# BSK.net
KiCad netlist of a schematic drawn in EAGLE
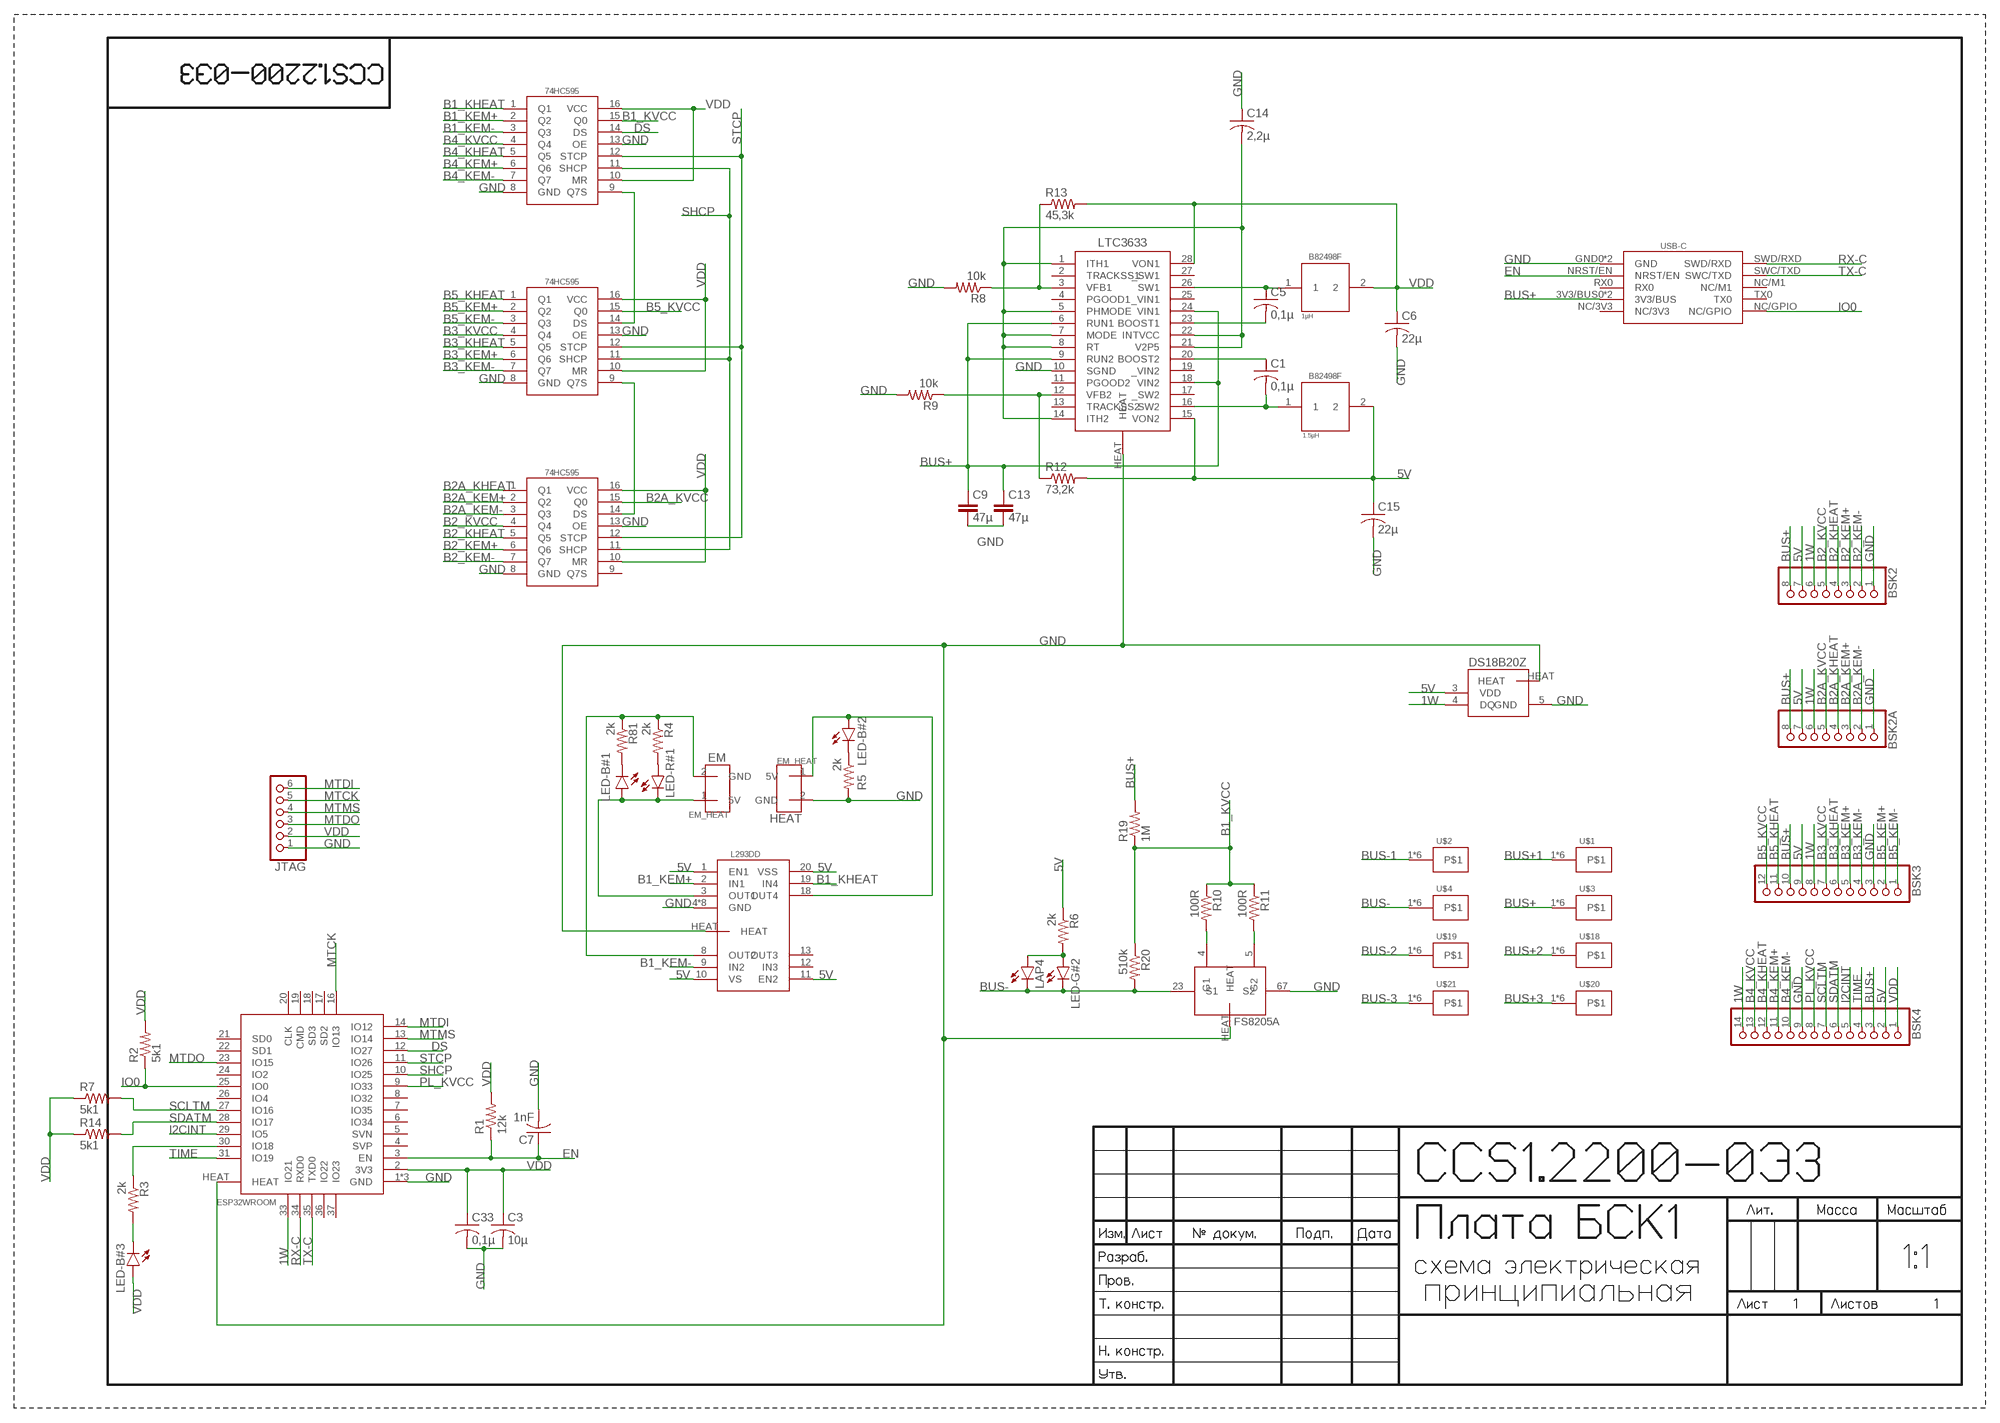
[diagram p0: schematic, sheet 1]

(export (version "E")
  (design (tool "Eeschema 10.0.6"))
  (components
    (comp (ref "74HC595#1")
      (value "74HC595")
      (footprint "eagle-import:74HC595")
      (libsource (lib "eagle-import") (part "74HC595"))
    )
    (comp (ref "74HC595#2")
      (value "74HC595")
      (footprint "eagle-import:74HC595")
      (libsource (lib "eagle-import") (part "74HC595"))
    )
    (comp (ref "74HC595#3")
      (value "74HC595")
      (footprint "eagle-import:74HC595")
      (libsource (lib "eagle-import") (part "74HC595"))
    )
    (comp (ref "B82498F#1")
      (value "1µH")
      (footprint "eagle-import:B82498F")
      (libsource (lib "eagle-import") (part "B82498F"))
    )
    (comp (ref "B82498F#2")
      (value "B82498F")
      (footprint "eagle-import:B82498F")
      (libsource (lib "eagle-import") (part "B82498F"))
    )
    (comp (ref "BSK2")
      (value "PINHD-1X8")
      (footprint "eagle-import:1X08")
      (libsource (lib "eagle-import") (part "PINHD-1X8"))
    )
    (comp (ref "BSK2A")
      (value "PINHD-1X8")
      (footprint "eagle-import:1X08")
      (libsource (lib "eagle-import") (part "PINHD-1X8"))
    )
    (comp (ref "BSK3")
      (value "PINHD-1X12")
      (footprint "eagle-import:1X12")
      (libsource (lib "eagle-import") (part "PINHD-1X12"))
    )
    (comp (ref "BSK4")
      (value "PINHD-1X14")
      (footprint "eagle-import:1X14")
      (libsource (lib "eagle-import") (part "PINHD-1X14"))
    )
    (comp (ref "C1")
      (value "0,1µ")
      (footprint "eagle-import:C0603")
      (libsource (lib "eagle-import") (part "C-USC0603"))
    )
    (comp (ref "C3")
      (value "10µ")
      (footprint "eagle-import:C1206")
      (libsource (lib "eagle-import") (part "C-USC1206"))
    )
    (comp (ref "C5")
      (value "0,1µ")
      (footprint "eagle-import:C0603")
      (libsource (lib "eagle-import") (part "C-USC0603"))
    )
    (comp (ref "C6")
      (value "22µ")
      (footprint "eagle-import:C1206")
      (libsource (lib "eagle-import") (part "C-USC1206"))
    )
    (comp (ref "C7")
      (value "1nF")
      (footprint "eagle-import:C0603")
      (libsource (lib "eagle-import") (part "C-USC0603"))
    )
    (comp (ref "C9")
      (value "47µ")
      (footprint "eagle-import:C1210")
      (libsource (lib "eagle-import") (part "C-EUC1210"))
    )
    (comp (ref "C13")
      (value "47µ")
      (footprint "eagle-import:C1210")
      (libsource (lib "eagle-import") (part "C-EUC1210"))
    )
    (comp (ref "C14")
      (value "2,2µ")
      (footprint "eagle-import:C0603")
      (libsource (lib "eagle-import") (part "C-USC0603"))
    )
    (comp (ref "C15")
      (value "22µ")
      (footprint "eagle-import:C1206")
      (libsource (lib "eagle-import") (part "C-USC1206"))
    )
    (comp (ref "C33")
      (value "0,1µ")
      (footprint "eagle-import:C0603")
      (libsource (lib "eagle-import") (part "C-USC0603"))
    )
    (comp (ref "DS18B20Z")
      (value "DS18B20Z")
      (footprint "eagle-import:DS18B20Z")
      (libsource (lib "eagle-import") (part "DS18B20Z"))
    )
    (comp (ref "EM")
      (value "EM_HEAT")
      (footprint "eagle-import:EM_HEAT")
      (libsource (lib "eagle-import") (part "EM_HEAT"))
    )
    (comp (ref "FS8205A")
      (value "FS8205A+")
      (footprint "eagle-import:FS8205A+")
      (libsource (lib "eagle-import") (part "FS8205A+"))
    )
    (comp (ref "HEATER")
      (value "EM_HEAT")
      (footprint "eagle-import:EM_HEAT")
      (libsource (lib "eagle-import") (part "EM_HEAT"))
    )
    (comp (ref "JTAG")
      (value "PINHD-1X6")
      (footprint "eagle-import:1X06")
      (libsource (lib "eagle-import") (part "PINHD-1X6"))
    )
    (comp (ref "L293DD")
      (value "L293DD")
      (footprint "eagle-import:L293DD")
      (libsource (lib "eagle-import") (part "L293DD"))
    )
    (comp (ref "LAP4")
      (value "LAP4-BOTTOM")
      (footprint "eagle-import:P47F-BOTTOM")
      (libsource (lib "eagle-import") (part "P4-BOTTOMLA"))
    )
    (comp (ref "LED-B#1")
      (value "LEDCHIPLED_0603")
      (footprint "eagle-import:CHIPLED_0603")
      (libsource (lib "eagle-import") (part "LEDCHIPLED_0603"))
    )
    (comp (ref "LED-B#2")
      (value "LEDCHIPLED_0603")
      (footprint "eagle-import:CHIPLED_0603")
      (libsource (lib "eagle-import") (part "LEDCHIPLED_0603"))
    )
    (comp (ref "LED-B#3")
      (value "LEDCHIPLED_0603")
      (footprint "eagle-import:CHIPLED_0603")
      (libsource (lib "eagle-import") (part "LEDCHIPLED_0603"))
    )
    (comp (ref "LED-G#2")
      (value "LEDCHIPLED_0603")
      (footprint "eagle-import:CHIPLED_0603")
      (libsource (lib "eagle-import") (part "LEDCHIPLED_0603"))
    )
    (comp (ref "LED-R#1")
      (value "LEDCHIPLED_0603")
      (footprint "eagle-import:CHIPLED_0603")
      (libsource (lib "eagle-import") (part "LEDCHIPLED_0603"))
    )
    (comp (ref "LTC3633")
      (value "LTC3633")
      (footprint "eagle-import:LTC3633")
      (libsource (lib "eagle-import") (part "LTC3633"))
    )
    (comp (ref "R1")
      (value "12k")
      (footprint "eagle-import:R0603")
      (libsource (lib "eagle-import") (part "R-US_R0603"))
    )
    (comp (ref "R2")
      (value "5k1")
      (footprint "eagle-import:R0603")
      (libsource (lib "eagle-import") (part "R-US_R0603"))
    )
    (comp (ref "R3")
      (value "2k")
      (footprint "eagle-import:R0603")
      (libsource (lib "eagle-import") (part "R-US_R0603"))
    )
    (comp (ref "R4")
      (value "2k")
      (footprint "eagle-import:R0603")
      (libsource (lib "eagle-import") (part "R-US_R0603"))
    )
    (comp (ref "R5")
      (value "2k")
      (footprint "eagle-import:R0603")
      (libsource (lib "eagle-import") (part "R-US_R0603"))
    )
    (comp (ref "R6")
      (value "2k")
      (footprint "eagle-import:R0603")
      (libsource (lib "eagle-import") (part "R-US_R0603"))
    )
    (comp (ref "R7")
      (value "5k1")
      (footprint "eagle-import:R0603")
      (libsource (lib "eagle-import") (part "R-US_R0603"))
    )
    (comp (ref "R8")
      (value "10k")
      (footprint "eagle-import:R0603")
      (libsource (lib "eagle-import") (part "R-US_R0603"))
    )
    (comp (ref "R9")
      (value "10k")
      (footprint "eagle-import:R0603")
      (libsource (lib "eagle-import") (part "R-US_R0603"))
    )
    (comp (ref "R10")
      (value "100R")
      (footprint "eagle-import:R0603")
      (libsource (lib "eagle-import") (part "R-US_R0603"))
    )
    (comp (ref "R11")
      (value "100R")
      (footprint "eagle-import:R0603")
      (libsource (lib "eagle-import") (part "R-US_R0603"))
    )
    (comp (ref "R12")
      (value "73,2k")
      (footprint "eagle-import:R0603")
      (libsource (lib "eagle-import") (part "R-US_R0603"))
    )
    (comp (ref "R13")
      (value "45,3k")
      (footprint "eagle-import:R0603")
      (libsource (lib "eagle-import") (part "R-US_R0603"))
    )
    (comp (ref "R14")
      (value "5k1")
      (footprint "eagle-import:R0603")
      (libsource (lib "eagle-import") (part "R-US_R0603"))
    )
    (comp (ref "R19")
      (value "1M")
      (footprint "eagle-import:R0603")
      (libsource (lib "eagle-import") (part "R-US_R0603"))
    )
    (comp (ref "R20")
      (value "510k")
      (footprint "eagle-import:R0603")
      (libsource (lib "eagle-import") (part "R-US_R0603"))
    )
    (comp (ref "R81")
      (value "2k")
      (footprint "eagle-import:R0603")
      (libsource (lib "eagle-import") (part "R-US_R0603"))
    )
    (comp (ref "U$1")
      (value "KCONNECT")
      (footprint "eagle-import:KCONNECT")
      (libsource (lib "eagle-import") (part "KCONNECT"))
    )
    (comp (ref "U$2")
      (value "KCONNECT")
      (footprint "eagle-import:KCONNECT")
      (libsource (lib "eagle-import") (part "KCONNECT"))
    )
    (comp (ref "U$3")
      (value "KCONNECT")
      (footprint "eagle-import:KCONNECT")
      (libsource (lib "eagle-import") (part "KCONNECT"))
    )
    (comp (ref "U$4")
      (value "KCONNECT")
      (footprint "eagle-import:KCONNECT")
      (libsource (lib "eagle-import") (part "KCONNECT"))
    )
    (comp (ref "U$13")
      (value "ESP32WROOM")
      (footprint "eagle-import:ESP32WROOM")
      (libsource (lib "eagle-import") (part "ESP32WROOM"))
    )
    (comp (ref "U$18")
      (value "KCONNECT")
      (footprint "eagle-import:KCONNECT")
      (libsource (lib "eagle-import") (part "KCONNECT"))
    )
    (comp (ref "U$19")
      (value "KCONNECT")
      (footprint "eagle-import:KCONNECT")
      (libsource (lib "eagle-import") (part "KCONNECT"))
    )
    (comp (ref "U$20")
      (value "KCONNECT")
      (footprint "eagle-import:KCONNECT")
      (libsource (lib "eagle-import") (part "KCONNECT"))
    )
    (comp (ref "U$21")
      (value "KCONNECT")
      (footprint "eagle-import:KCONNECT")
      (libsource (lib "eagle-import") (part "KCONNECT"))
    )
    (comp (ref "USB-C")
      (value "USB-C")
      (footprint "eagle-import:USB-C")
      (fields (field (name "SPICEPREFIX") "X"))
      (libsource (lib "eagle-import") (part "USB-C"))
    )
  )
  (nets
    (net (code "1") (name "/1W") (class "Default")
      (node (ref "BSK2") (pin "6") (pinfunction "6_6") (pintype "passive"))
      (node (ref "BSK2A") (pin "6") (pinfunction "6_6") (pintype "passive"))
      (node (ref "BSK3") (pin "8") (pinfunction "8_8") (pintype "passive"))
      (node (ref "BSK4") (pin "14") (pinfunction "14_14") (pintype "passive"))
      (node (ref "DS18B20Z") (pin "4") (pinfunction "DQ_4") (pintype "bidirectional"))
      (node (ref "U$13") (pin "33") (pinfunction "IO21_33") (pintype "bidirectional"))
    )
    (net (code "2") (name "/5V") (class "Default")
      (node (ref "B82498F#2") (pin "2") (pinfunction "2_2") (pintype "bidirectional"))
      (node (ref "BSK2") (pin "7") (pinfunction "7_7") (pintype "passive"))
      (node (ref "BSK2A") (pin "7") (pinfunction "7_7") (pintype "passive"))
      (node (ref "BSK3") (pin "9") (pinfunction "9_9") (pintype "passive"))
      (node (ref "BSK4") (pin "2") (pinfunction "2_2") (pintype "passive"))
      (node (ref "C15") (pin "1") (pinfunction "1_1") (pintype "passive"))
      (node (ref "DS18B20Z") (pin "3") (pinfunction "VDD_3") (pintype "bidirectional"))
      (node (ref "L293DD") (pin "1") (pinfunction "EN1_1") (pintype "bidirectional"))
      (node (ref "L293DD") (pin "10") (pinfunction "VS_10") (pintype "bidirectional"))
      (node (ref "L293DD") (pin "11") (pinfunction "EN2_11") (pintype "bidirectional"))
      (node (ref "L293DD") (pin "20") (pinfunction "VSS_20") (pintype "bidirectional"))
      (node (ref "LTC3633") (pin "15") (pinfunction "VON2_15") (pintype "bidirectional"))
      (node (ref "R12") (pin "2") (pinfunction "2_2") (pintype "passive"))
      (node (ref "R6") (pin "1") (pinfunction "1_1") (pintype "passive"))
    )
    (net (code "3") (name "/B1_KEM+") (class "Default")
      (node (ref "74HC595#1") (pin "2") (pinfunction "Q2_2") (pintype "bidirectional"))
      (node (ref "L293DD") (pin "2") (pinfunction "IN1_2") (pintype "bidirectional"))
    )
    (net (code "4") (name "/B1_KEM-") (class "Default")
      (node (ref "74HC595#1") (pin "3") (pinfunction "Q3_3") (pintype "bidirectional"))
      (node (ref "L293DD") (pin "9") (pinfunction "IN2_9") (pintype "bidirectional"))
    )
    (net (code "5") (name "/B1_KHEAT") (class "Default")
      (node (ref "74HC595#1") (pin "1") (pinfunction "Q1_1") (pintype "bidirectional"))
      (node (ref "L293DD") (pin "19") (pinfunction "IN4_19") (pintype "bidirectional"))
    )
    (net (code "6") (name "/B1_KVCC") (class "Default")
      (node (ref "74HC595#1") (pin "15") (pinfunction "Q0_15") (pintype "bidirectional"))
      (node (ref "R10") (pin "1") (pinfunction "1_1") (pintype "passive"))
      (node (ref "R11") (pin "1") (pinfunction "1_1") (pintype "passive"))
      (node (ref "R19") (pin "1") (pinfunction "1_1") (pintype "passive"))
      (node (ref "R20") (pin "1") (pinfunction "1_1") (pintype "passive"))
    )
    (net (code "7") (name "/B2A_KEM+") (class "Default")
      (node (ref "74HC595#3") (pin "2") (pinfunction "Q2_2") (pintype "bidirectional"))
      (node (ref "BSK2A") (pin "3") (pinfunction "3_3") (pintype "passive"))
    )
    (net (code "8") (name "/B2A_KEM-") (class "Default")
      (node (ref "74HC595#3") (pin "3") (pinfunction "Q3_3") (pintype "bidirectional"))
      (node (ref "BSK2A") (pin "2") (pinfunction "2_2") (pintype "passive"))
    )
    (net (code "9") (name "/B2A_KHEAT") (class "Default")
      (node (ref "74HC595#3") (pin "1") (pinfunction "Q1_1") (pintype "bidirectional"))
      (node (ref "BSK2A") (pin "4") (pinfunction "4_4") (pintype "passive"))
    )
    (net (code "10") (name "/B2A_KVCC") (class "Default")
      (node (ref "74HC595#3") (pin "15") (pinfunction "Q0_15") (pintype "bidirectional"))
      (node (ref "BSK2A") (pin "5") (pinfunction "5_5") (pintype "passive"))
    )
    (net (code "11") (name "/B2_KEM+") (class "Default")
      (node (ref "74HC595#3") (pin "6") (pinfunction "Q6_6") (pintype "bidirectional"))
      (node (ref "BSK2") (pin "3") (pinfunction "3_3") (pintype "passive"))
    )
    (net (code "12") (name "/B2_KEM-") (class "Default")
      (node (ref "74HC595#3") (pin "7") (pinfunction "Q7_7") (pintype "bidirectional"))
      (node (ref "BSK2") (pin "2") (pinfunction "2_2") (pintype "passive"))
    )
    (net (code "13") (name "/B2_KHEAT") (class "Default")
      (node (ref "74HC595#3") (pin "5") (pinfunction "Q5_5") (pintype "bidirectional"))
      (node (ref "BSK2") (pin "4") (pinfunction "4_4") (pintype "passive"))
    )
    (net (code "14") (name "/B2_KVCC") (class "Default")
      (node (ref "74HC595#3") (pin "4") (pinfunction "Q4_4") (pintype "bidirectional"))
      (node (ref "BSK2") (pin "5") (pinfunction "5_5") (pintype "passive"))
    )
    (net (code "15") (name "/B3_KEM+") (class "Default")
      (node (ref "74HC595#2") (pin "6") (pinfunction "Q6_6") (pintype "bidirectional"))
      (node (ref "BSK3") (pin "5") (pinfunction "5_5") (pintype "passive"))
    )
    (net (code "16") (name "/B3_KEM-") (class "Default")
      (node (ref "74HC595#2") (pin "7") (pinfunction "Q7_7") (pintype "bidirectional"))
      (node (ref "BSK3") (pin "4") (pinfunction "4_4") (pintype "passive"))
    )
    (net (code "17") (name "/B3_KHEAT") (class "Default")
      (node (ref "74HC595#2") (pin "5") (pinfunction "Q5_5") (pintype "bidirectional"))
      (node (ref "BSK3") (pin "6") (pinfunction "6_6") (pintype "passive"))
    )
    (net (code "18") (name "/B3_KVCC") (class "Default")
      (node (ref "74HC595#2") (pin "4") (pinfunction "Q4_4") (pintype "bidirectional"))
      (node (ref "BSK3") (pin "7") (pinfunction "7_7") (pintype "passive"))
    )
    (net (code "19") (name "/B4_KEM+") (class "Default")
      (node (ref "74HC595#1") (pin "6") (pinfunction "Q6_6") (pintype "bidirectional"))
      (node (ref "BSK4") (pin "11") (pinfunction "11_11") (pintype "passive"))
    )
    (net (code "20") (name "/B4_KEM-") (class "Default")
      (node (ref "74HC595#1") (pin "7") (pinfunction "Q7_7") (pintype "bidirectional"))
      (node (ref "BSK4") (pin "10") (pinfunction "10_10") (pintype "passive"))
    )
    (net (code "21") (name "/B4_KHEAT") (class "Default")
      (node (ref "74HC595#1") (pin "5") (pinfunction "Q5_5") (pintype "bidirectional"))
      (node (ref "BSK4") (pin "12") (pinfunction "12_12") (pintype "passive"))
    )
    (net (code "22") (name "/B4_KVCC") (class "Default")
      (node (ref "74HC595#1") (pin "4") (pinfunction "Q4_4") (pintype "bidirectional"))
      (node (ref "BSK4") (pin "13") (pinfunction "13_13") (pintype "passive"))
    )
    (net (code "23") (name "/B5_KEM+") (class "Default")
      (node (ref "74HC595#2") (pin "2") (pinfunction "Q2_2") (pintype "bidirectional"))
      (node (ref "BSK3") (pin "2") (pinfunction "2_2") (pintype "passive"))
    )
    (net (code "24") (name "/B5_KEM-") (class "Default")
      (node (ref "74HC595#2") (pin "3") (pinfunction "Q3_3") (pintype "bidirectional"))
      (node (ref "BSK3") (pin "1") (pinfunction "1_1") (pintype "passive"))
    )
    (net (code "25") (name "/B5_KHEAT") (class "Default")
      (node (ref "74HC595#2") (pin "1") (pinfunction "Q1_1") (pintype "bidirectional"))
      (node (ref "BSK3") (pin "11") (pinfunction "11_11") (pintype "passive"))
    )
    (net (code "26") (name "/B5_KVCC") (class "Default")
      (node (ref "74HC595#2") (pin "15") (pinfunction "Q0_15") (pintype "bidirectional"))
      (node (ref "BSK3") (pin "12") (pinfunction "12_12") (pintype "passive"))
    )
    (net (code "27") (name "/BUS+") (class "Default")
      (node (ref "BSK2") (pin "8") (pinfunction "8_8") (pintype "passive"))
      (node (ref "BSK2A") (pin "8") (pinfunction "8_8") (pintype "passive"))
      (node (ref "BSK3") (pin "10") (pinfunction "10_10") (pintype "passive"))
      (node (ref "BSK4") (pin "3") (pinfunction "3_3") (pintype "passive"))
      (node (ref "C13") (pin "1") (pinfunction "1_1") (pintype "passive"))
      (node (ref "C9") (pin "1") (pinfunction "1_1") (pintype "passive"))
      (node (ref "LTC3633") (pin "18") (pinfunction "VIN2_18") (pintype "bidirectional"))
      (node (ref "LTC3633") (pin "24") (pinfunction "VIN1_24") (pintype "bidirectional"))
      (node (ref "LTC3633") (pin "6") (pinfunction "RUN1_6") (pintype "bidirectional"))
      (node (ref "LTC3633") (pin "9") (pinfunction "RUN2_9") (pintype "bidirectional"))
      (node (ref "R19") (pin "2") (pinfunction "2_2") (pintype "passive"))
      (node (ref "U$3") (pin "1") (pinfunction "P$1_1") (pintype "bidirectional"))
      (node (ref "U$3") (pin "2") (pinfunction "P$1_2") (pintype "bidirectional"))
      (node (ref "U$3") (pin "3") (pinfunction "P$1_3") (pintype "bidirectional"))
      (node (ref "U$3") (pin "4") (pinfunction "P$1_4") (pintype "bidirectional"))
      (node (ref "U$3") (pin "P$1") (pinfunction "P$1_P$1") (pintype "bidirectional"))
      (node (ref "U$3") (pin "P$2") (pinfunction "P$1_P$2") (pintype "bidirectional"))
      (node (ref "USB-C") (pin "3V3/BUS0") (pinfunction "3V3/BUS_3V3/BUS0") (pintype "bidirectional"))
      (node (ref "USB-C") (pin "3V3/BUS1") (pinfunction "3V3/BUS_3V3/BUS1") (pintype "bidirectional"))
    )
    (net (code "28") (name "/BUS+1") (class "Default")
      (node (ref "U$1") (pin "1") (pinfunction "P$1_1") (pintype "bidirectional"))
      (node (ref "U$1") (pin "2") (pinfunction "P$1_2") (pintype "bidirectional"))
      (node (ref "U$1") (pin "3") (pinfunction "P$1_3") (pintype "bidirectional"))
      (node (ref "U$1") (pin "4") (pinfunction "P$1_4") (pintype "bidirectional"))
      (node (ref "U$1") (pin "P$1") (pinfunction "P$1_P$1") (pintype "bidirectional"))
      (node (ref "U$1") (pin "P$2") (pinfunction "P$1_P$2") (pintype "bidirectional"))
    )
    (net (code "29") (name "/BUS+2") (class "Default")
      (node (ref "U$18") (pin "1") (pinfunction "P$1_1") (pintype "bidirectional"))
      (node (ref "U$18") (pin "2") (pinfunction "P$1_2") (pintype "bidirectional"))
      (node (ref "U$18") (pin "3") (pinfunction "P$1_3") (pintype "bidirectional"))
      (node (ref "U$18") (pin "4") (pinfunction "P$1_4") (pintype "bidirectional"))
      (node (ref "U$18") (pin "P$1") (pinfunction "P$1_P$1") (pintype "bidirectional"))
      (node (ref "U$18") (pin "P$2") (pinfunction "P$1_P$2") (pintype "bidirectional"))
    )
    (net (code "30") (name "/BUS+3") (class "Default")
      (node (ref "U$20") (pin "1") (pinfunction "P$1_1") (pintype "bidirectional"))
      (node (ref "U$20") (pin "2") (pinfunction "P$1_2") (pintype "bidirectional"))
      (node (ref "U$20") (pin "3") (pinfunction "P$1_3") (pintype "bidirectional"))
      (node (ref "U$20") (pin "4") (pinfunction "P$1_4") (pintype "bidirectional"))
      (node (ref "U$20") (pin "P$1") (pinfunction "P$1_P$1") (pintype "bidirectional"))
      (node (ref "U$20") (pin "P$2") (pinfunction "P$1_P$2") (pintype "bidirectional"))
    )
    (net (code "31") (name "/BUS-") (class "Default")
      (node (ref "FS8205A") (pin "23") (pinfunction "S1_23") (pintype "bidirectional"))
      (node (ref "LAP4") (pin "C") (pinfunction "C_C") (pintype "passive"))
      (node (ref "LED-G#2") (pin "C") (pinfunction "C_C") (pintype "passive"))
      (node (ref "R20") (pin "2") (pinfunction "2_2") (pintype "passive"))
      (node (ref "U$4") (pin "1") (pinfunction "P$1_1") (pintype "bidirectional"))
      (node (ref "U$4") (pin "2") (pinfunction "P$1_2") (pintype "bidirectional"))
      (node (ref "U$4") (pin "3") (pinfunction "P$1_3") (pintype "bidirectional"))
      (node (ref "U$4") (pin "4") (pinfunction "P$1_4") (pintype "bidirectional"))
      (node (ref "U$4") (pin "P$1") (pinfunction "P$1_P$1") (pintype "bidirectional"))
      (node (ref "U$4") (pin "P$2") (pinfunction "P$1_P$2") (pintype "bidirectional"))
    )
    (net (code "32") (name "/BUS-1") (class "Default")
      (node (ref "U$2") (pin "1") (pinfunction "P$1_1") (pintype "bidirectional"))
      (node (ref "U$2") (pin "2") (pinfunction "P$1_2") (pintype "bidirectional"))
      (node (ref "U$2") (pin "3") (pinfunction "P$1_3") (pintype "bidirectional"))
      (node (ref "U$2") (pin "4") (pinfunction "P$1_4") (pintype "bidirectional"))
      (node (ref "U$2") (pin "P$1") (pinfunction "P$1_P$1") (pintype "bidirectional"))
      (node (ref "U$2") (pin "P$2") (pinfunction "P$1_P$2") (pintype "bidirectional"))
    )
    (net (code "33") (name "/BUS-2") (class "Default")
      (node (ref "U$19") (pin "1") (pinfunction "P$1_1") (pintype "bidirectional"))
      (node (ref "U$19") (pin "2") (pinfunction "P$1_2") (pintype "bidirectional"))
      (node (ref "U$19") (pin "3") (pinfunction "P$1_3") (pintype "bidirectional"))
      (node (ref "U$19") (pin "4") (pinfunction "P$1_4") (pintype "bidirectional"))
      (node (ref "U$19") (pin "P$1") (pinfunction "P$1_P$1") (pintype "bidirectional"))
      (node (ref "U$19") (pin "P$2") (pinfunction "P$1_P$2") (pintype "bidirectional"))
    )
    (net (code "34") (name "/BUS-3") (class "Default")
      (node (ref "U$21") (pin "1") (pinfunction "P$1_1") (pintype "bidirectional"))
      (node (ref "U$21") (pin "2") (pinfunction "P$1_2") (pintype "bidirectional"))
      (node (ref "U$21") (pin "3") (pinfunction "P$1_3") (pintype "bidirectional"))
      (node (ref "U$21") (pin "4") (pinfunction "P$1_4") (pintype "bidirectional"))
      (node (ref "U$21") (pin "P$1") (pinfunction "P$1_P$1") (pintype "bidirectional"))
      (node (ref "U$21") (pin "P$2") (pinfunction "P$1_P$2") (pintype "bidirectional"))
    )
    (net (code "35") (name "/DS") (class "Default")
      (node (ref "74HC595#1") (pin "14") (pinfunction "DS_14") (pintype "bidirectional"))
      (node (ref "U$13") (pin "12") (pinfunction "IO27_12") (pintype "bidirectional"))
    )
    (net (code "36") (name "/EN") (class "Default")
      (node (ref "C7") (pin "1") (pinfunction "1_1") (pintype "passive"))
      (node (ref "R1") (pin "1") (pinfunction "1_1") (pintype "passive"))
      (node (ref "U$13") (pin "3") (pinfunction "EN_3") (pintype "bidirectional"))
      (node (ref "USB-C") (pin "NRST/EN") (pinfunction "NRST/EN_NRST/EN") (pintype "bidirectional"))
    )
    (net (code "37") (name "/GND") (class "Default")
      (node (ref "74HC595#1") (pin "13") (pinfunction "OE_13") (pintype "bidirectional"))
      (node (ref "74HC595#1") (pin "8") (pinfunction "GND_8") (pintype "bidirectional"))
      (node (ref "74HC595#2") (pin "13") (pinfunction "OE_13") (pintype "bidirectional"))
      (node (ref "74HC595#2") (pin "8") (pinfunction "GND_8") (pintype "bidirectional"))
      (node (ref "74HC595#3") (pin "13") (pinfunction "OE_13") (pintype "bidirectional"))
      (node (ref "74HC595#3") (pin "8") (pinfunction "GND_8") (pintype "bidirectional"))
      (node (ref "BSK2") (pin "1") (pinfunction "1_1") (pintype "passive"))
      (node (ref "BSK2A") (pin "1") (pinfunction "1_1") (pintype "passive"))
      (node (ref "BSK3") (pin "3") (pinfunction "3_3") (pintype "passive"))
      (node (ref "BSK4") (pin "9") (pinfunction "9_9") (pintype "passive"))
      (node (ref "C13") (pin "2") (pinfunction "2_2") (pintype "passive"))
      (node (ref "C14") (pin "1") (pinfunction "1_1") (pintype "passive"))
      (node (ref "C15") (pin "2") (pinfunction "2_2") (pintype "passive"))
      (node (ref "C3") (pin "2") (pinfunction "2_2") (pintype "passive"))
      (node (ref "C33") (pin "2") (pinfunction "2_2") (pintype "passive"))
      (node (ref "C6") (pin "2") (pinfunction "2_2") (pintype "passive"))
      (node (ref "C7") (pin "2") (pinfunction "2_2") (pintype "passive"))
      (node (ref "C9") (pin "2") (pinfunction "2_2") (pintype "passive"))
      (node (ref "DS18B20Z") (pin "5") (pinfunction "GND_5") (pintype "bidirectional"))
      (node (ref "DS18B20Z") (pin "HEAT") (pinfunction "HEAT_HEAT") (pintype "bidirectional"))
      (node (ref "FS8205A") (pin "67") (pinfunction "S2_67") (pintype "bidirectional"))
      (node (ref "FS8205A") (pin "HEAT") (pinfunction "HEAT_HEAT") (pintype "bidirectional"))
      (node (ref "HEATER") (pin "2") (pinfunction "GND_2") (pintype "bidirectional"))
      (node (ref "JTAG") (pin "1") (pinfunction "1_1") (pintype "passive"))
      (node (ref "L293DD") (pin "14") (pinfunction "GND_14") (pintype "bidirectional"))
      (node (ref "L293DD") (pin "15") (pinfunction "GND_15") (pintype "bidirectional"))
      (node (ref "L293DD") (pin "16") (pinfunction "GND_16") (pintype "bidirectional"))
      (node (ref "L293DD") (pin "17") (pinfunction "GND_17") (pintype "bidirectional"))
      (node (ref "L293DD") (pin "4") (pinfunction "GND_4") (pintype "bidirectional"))
      (node (ref "L293DD") (pin "5") (pinfunction "GND_5") (pintype "bidirectional"))
      (node (ref "L293DD") (pin "6") (pinfunction "GND_6") (pintype "bidirectional"))
      (node (ref "L293DD") (pin "7") (pinfunction "GND_7") (pintype "bidirectional"))
      (node (ref "L293DD") (pin "HEAT") (pinfunction "HEAT_HEAT") (pintype "bidirectional"))
      (node (ref "LTC3633") (pin "10") (pinfunction "SGND_10") (pintype "bidirectional"))
      (node (ref "LTC3633") (pin "HEAT") (pinfunction "HEAT_HEAT") (pintype "bidirectional"))
      (node (ref "R5") (pin "2") (pinfunction "2_2") (pintype "passive"))
      (node (ref "R8") (pin "2") (pinfunction "2_2") (pintype "passive"))
      (node (ref "R9") (pin "2") (pinfunction "2_2") (pintype "passive"))
      (node (ref "U$13") (pin "1") (pinfunction "GND_1") (pintype "bidirectional"))
      (node (ref "U$13") (pin "15") (pinfunction "GND_15") (pintype "bidirectional"))
      (node (ref "U$13") (pin "38") (pinfunction "GND_38") (pintype "bidirectional"))
      (node (ref "U$13") (pin "HEAT") (pinfunction "HEAT_HEAT") (pintype "bidirectional"))
      (node (ref "USB-C") (pin "GND0") (pinfunction "GND_GND0") (pintype "bidirectional"))
      (node (ref "USB-C") (pin "GND1") (pinfunction "GND_GND1") (pintype "bidirectional"))
    )
    (net (code "38") (name "/I2CINT") (class "Default")
      (node (ref "BSK4") (pin "5") (pinfunction "5_5") (pintype "passive"))
      (node (ref "U$13") (pin "29") (pinfunction "IO5_29") (pintype "bidirectional"))
    )
    (net (code "39") (name "/IO0") (class "Default")
      (node (ref "R2") (pin "1") (pinfunction "1_1") (pintype "passive"))
      (node (ref "U$13") (pin "25") (pinfunction "IO0_25") (pintype "bidirectional"))
      (node (ref "USB-C") (pin "NC/GPIO") (pinfunction "NC/GPIO_NC/GPIO") (pintype "bidirectional"))
    )
    (net (code "40") (name "/MTCK") (class "Default")
      (node (ref "JTAG") (pin "5") (pinfunction "5_5") (pintype "passive"))
      (node (ref "U$13") (pin "16") (pinfunction "IO13_16") (pintype "bidirectional"))
    )
    (net (code "41") (name "/MTDI") (class "Default")
      (node (ref "JTAG") (pin "6") (pinfunction "6_6") (pintype "passive"))
      (node (ref "U$13") (pin "14") (pinfunction "IO12_14") (pintype "bidirectional"))
    )
    (net (code "42") (name "/MTDO") (class "Default")
      (node (ref "JTAG") (pin "3") (pinfunction "3_3") (pintype "passive"))
      (node (ref "U$13") (pin "23") (pinfunction "IO15_23") (pintype "bidirectional"))
    )
    (net (code "43") (name "/MTMS") (class "Default")
      (node (ref "JTAG") (pin "4") (pinfunction "4_4") (pintype "passive"))
      (node (ref "U$13") (pin "13") (pinfunction "IO14_13") (pintype "bidirectional"))
    )
    (net (code "44") (name "/PL_KVCC") (class "Default")
      (node (ref "BSK4") (pin "8") (pinfunction "8_8") (pintype "passive"))
      (node (ref "U$13") (pin "9") (pinfunction "IO33_9") (pintype "bidirectional"))
    )
    (net (code "45") (name "/RX-C") (class "Default")
      (node (ref "U$13") (pin "34") (pinfunction "RXD0_34") (pintype "bidirectional"))
      (node (ref "USB-C") (pin "SWD/RXD") (pinfunction "SWD/RXD_SWD/RXD") (pintype "bidirectional"))
    )
    (net (code "46") (name "/SCLTM") (class "Default")
      (node (ref "BSK4") (pin "7") (pinfunction "7_7") (pintype "passive"))
      (node (ref "R7") (pin "2") (pinfunction "2_2") (pintype "passive"))
      (node (ref "U$13") (pin "27") (pinfunction "IO16_27") (pintype "bidirectional"))
    )
    (net (code "47") (name "/SDATM") (class "Default")
      (node (ref "BSK4") (pin "6") (pinfunction "6_6") (pintype "passive"))
      (node (ref "R14") (pin "2") (pinfunction "2_2") (pintype "passive"))
      (node (ref "U$13") (pin "28") (pinfunction "IO17_28") (pintype "bidirectional"))
    )
    (net (code "48") (name "/SHCP") (class "Default")
      (node (ref "74HC595#1") (pin "11") (pinfunction "SHCP_11") (pintype "bidirectional"))
      (node (ref "74HC595#2") (pin "11") (pinfunction "SHCP_11") (pintype "bidirectional"))
      (node (ref "74HC595#3") (pin "11") (pinfunction "SHCP_11") (pintype "bidirectional"))
      (node (ref "U$13") (pin "10") (pinfunction "IO25_10") (pintype "bidirectional"))
    )
    (net (code "49") (name "/STCP") (class "Default")
      (node (ref "74HC595#1") (pin "12") (pinfunction "STCP_12") (pintype "bidirectional"))
      (node (ref "74HC595#2") (pin "12") (pinfunction "STCP_12") (pintype "bidirectional"))
      (node (ref "74HC595#3") (pin "12") (pinfunction "STCP_12") (pintype "bidirectional"))
      (node (ref "U$13") (pin "11") (pinfunction "IO26_11") (pintype "bidirectional"))
    )
    (net (code "50") (name "/TIME") (class "Default")
      (node (ref "BSK4") (pin "4") (pinfunction "4_4") (pintype "passive"))
      (node (ref "U$13") (pin "31") (pinfunction "IO19_31") (pintype "bidirectional"))
    )
    (net (code "51") (name "/TX-C") (class "Default")
      (node (ref "U$13") (pin "35") (pinfunction "TXD0_35") (pintype "bidirectional"))
      (node (ref "USB-C") (pin "SWC/TXD") (pinfunction "SWC/TXD_SWC/TXD") (pintype "bidirectional"))
    )
    (net (code "52") (name "/VDD") (class "Default")
      (node (ref "74HC595#1") (pin "10") (pinfunction "MR_10") (pintype "bidirectional"))
      (node (ref "74HC595#1") (pin "16") (pinfunction "VCC_16") (pintype "bidirectional"))
      (node (ref "74HC595#2") (pin "10") (pinfunction "MR_10") (pintype "bidirectional"))
      (node (ref "74HC595#2") (pin "16") (pinfunction "VCC_16") (pintype "bidirectional"))
      (node (ref "74HC595#3") (pin "10") (pinfunction "MR_10") (pintype "bidirectional"))
      (node (ref "74HC595#3") (pin "16") (pinfunction "VCC_16") (pintype "bidirectional"))
      (node (ref "B82498F#1") (pin "2") (pinfunction "2_2") (pintype "bidirectional"))
      (node (ref "BSK4") (pin "1") (pinfunction "1_1") (pintype "passive"))
      (node (ref "C3") (pin "1") (pinfunction "1_1") (pintype "passive"))
      (node (ref "C33") (pin "1") (pinfunction "1_1") (pintype "passive"))
      (node (ref "C6") (pin "1") (pinfunction "1_1") (pintype "passive"))
      (node (ref "JTAG") (pin "2") (pinfunction "2_2") (pintype "passive"))
      (node (ref "LED-B#3") (pin "A") (pinfunction "A_A") (pintype "passive"))
      (node (ref "LTC3633") (pin "28") (pinfunction "VON1_28") (pintype "bidirectional"))
      (node (ref "R1") (pin "2") (pinfunction "2_2") (pintype "passive"))
      (node (ref "R13") (pin "2") (pinfunction "2_2") (pintype "passive"))
      (node (ref "R14") (pin "1") (pinfunction "1_1") (pintype "passive"))
      (node (ref "R2") (pin "2") (pinfunction "2_2") (pintype "passive"))
      (node (ref "R7") (pin "1") (pinfunction "1_1") (pintype "passive"))
      (node (ref "U$13") (pin "2") (pinfunction "3V3_2") (pintype "bidirectional"))
    )
    (net (code "53") (name "Net-(74HC595#1-Q7S)") (class "Default")
      (node (ref "74HC595#1") (pin "9") (pinfunction "Q7S_9") (pintype "bidirectional"))
      (node (ref "74HC595#2") (pin "14") (pinfunction "DS_14") (pintype "bidirectional"))
    )
    (net (code "54") (name "Net-(74HC595#2-Q7S)") (class "Default")
      (node (ref "74HC595#2") (pin "9") (pinfunction "Q7S_9") (pintype "bidirectional"))
      (node (ref "74HC595#3") (pin "14") (pinfunction "DS_14") (pintype "bidirectional"))
    )
    (net (code "55") (name "Net-(EM-5V)") (class "Default")
      (node (ref "EM") (pin "1") (pinfunction "5V_1") (pintype "bidirectional"))
      (node (ref "L293DD") (pin "3") (pinfunction "OUT1_3") (pintype "bidirectional"))
      (node (ref "LED-B#1") (pin "A") (pinfunction "A_A") (pintype "passive"))
      (node (ref "LED-R#1") (pin "C") (pinfunction "C_C") (pintype "passive"))
    )
    (net (code "56") (name "Net-(EM-GND)") (class "Default")
      (node (ref "EM") (pin "2") (pinfunction "GND_2") (pintype "bidirectional"))
      (node (ref "L293DD") (pin "8") (pinfunction "OUT2_8") (pintype "bidirectional"))
      (node (ref "R4") (pin "1") (pinfunction "1_1") (pintype "passive"))
      (node (ref "R81") (pin "1") (pinfunction "1_1") (pintype "passive"))
    )
    (net (code "57") (name "Net-(FS8205A-G1)") (class "Default")
      (node (ref "FS8205A") (pin "4") (pinfunction "G1_4") (pintype "bidirectional"))
      (node (ref "R10") (pin "2") (pinfunction "2_2") (pintype "passive"))
    )
    (net (code "58") (name "Net-(FS8205A-G2)") (class "Default")
      (node (ref "FS8205A") (pin "5") (pinfunction "G2_5") (pintype "bidirectional"))
      (node (ref "R11") (pin "2") (pinfunction "2_2") (pintype "passive"))
    )
    (net (code "59") (name "Net-(HEATER-5V)") (class "Default")
      (node (ref "HEATER") (pin "1") (pinfunction "5V_1") (pintype "bidirectional"))
      (node (ref "L293DD") (pin "18") (pinfunction "OUT4_18") (pintype "bidirectional"))
      (node (ref "LED-B#2") (pin "A") (pinfunction "A_A") (pintype "passive"))
    )
    (net (code "60") (name "Net-(LAP4-PadA)") (class "Default")
      (node (ref "LAP4") (pin "A") (pinfunction "A_A") (pintype "passive"))
      (node (ref "LED-G#2") (pin "A") (pinfunction "A_A") (pintype "passive"))
      (node (ref "R6") (pin "2") (pinfunction "2_2") (pintype "passive"))
    )
    (net (code "61") (name "Net-(LED-B#1-PadC)") (class "Default")
      (node (ref "LED-B#1") (pin "C") (pinfunction "C_C") (pintype "passive"))
      (node (ref "R81") (pin "2") (pinfunction "2_2") (pintype "passive"))
    )
    (net (code "62") (name "Net-(LED-B#2-PadC)") (class "Default")
      (node (ref "LED-B#2") (pin "C") (pinfunction "C_C") (pintype "passive"))
      (node (ref "R5") (pin "1") (pinfunction "1_1") (pintype "passive"))
    )
    (net (code "63") (name "Net-(LED-B#3-PadC)") (class "Default")
      (node (ref "LED-B#3") (pin "C") (pinfunction "C_C") (pintype "passive"))
      (node (ref "R3") (pin "2") (pinfunction "2_2") (pintype "passive"))
    )
    (net (code "64") (name "Net-(LED-R#1-PadA)") (class "Default")
      (node (ref "LED-R#1") (pin "A") (pinfunction "A_A") (pintype "passive"))
      (node (ref "R4") (pin "2") (pinfunction "2_2") (pintype "passive"))
    )
    (net (code "65") (name "Net-(LTC3633-BOOST1)") (class "Default")
      (node (ref "C5") (pin "2") (pinfunction "2_2") (pintype "passive"))
      (node (ref "LTC3633") (pin "23") (pinfunction "BOOST1_23") (pintype "bidirectional"))
    )
    (net (code "66") (name "Net-(LTC3633-BOOST2)") (class "Default")
      (node (ref "C1") (pin "1") (pinfunction "1_1") (pintype "passive"))
      (node (ref "LTC3633") (pin "20") (pinfunction "BOOST2_20") (pintype "bidirectional"))
    )
    (net (code "67") (name "Net-(LTC3633-INTVCC)") (class "Default")
      (node (ref "C14") (pin "2") (pinfunction "2_2") (pintype "passive"))
      (node (ref "LTC3633") (pin "1") (pinfunction "ITH1_1") (pintype "bidirectional"))
      (node (ref "LTC3633") (pin "14") (pinfunction "ITH2_14") (pintype "bidirectional"))
      (node (ref "LTC3633") (pin "21") (pinfunction "V2P5_21") (pintype "bidirectional"))
      (node (ref "LTC3633") (pin "22") (pinfunction "INTVCC_22") (pintype "bidirectional"))
      (node (ref "LTC3633") (pin "5") (pinfunction "PHMODE_5") (pintype "bidirectional"))
      (node (ref "LTC3633") (pin "7") (pinfunction "MODE_7") (pintype "bidirectional"))
      (node (ref "LTC3633") (pin "8") (pinfunction "RT_8") (pintype "bidirectional"))
    )
    (net (code "68") (name "Net-(LTC3633-SW1)") (class "Default")
      (node (ref "B82498F#1") (pin "1") (pinfunction "1_1") (pintype "bidirectional"))
      (node (ref "C5") (pin "1") (pinfunction "1_1") (pintype "passive"))
      (node (ref "LTC3633") (pin "26") (pinfunction "SW1_26") (pintype "bidirectional"))
    )
    (net (code "69") (name "Net-(LTC3633-SW2)") (class "Default")
      (node (ref "B82498F#2") (pin "1") (pinfunction "1_1") (pintype "bidirectional"))
      (node (ref "C1") (pin "2") (pinfunction "2_2") (pintype "passive"))
      (node (ref "LTC3633") (pin "16") (pinfunction "SW2_16") (pintype "bidirectional"))
    )
    (net (code "70") (name "Net-(LTC3633-VFB1)") (class "Default")
      (node (ref "LTC3633") (pin "3") (pinfunction "VFB1_3") (pintype "bidirectional"))
      (node (ref "R13") (pin "1") (pinfunction "1_1") (pintype "passive"))
      (node (ref "R8") (pin "1") (pinfunction "1_1") (pintype "passive"))
    )
    (net (code "71") (name "Net-(LTC3633-VFB2)") (class "Default")
      (node (ref "LTC3633") (pin "12") (pinfunction "VFB2_12") (pintype "bidirectional"))
      (node (ref "R12") (pin "1") (pinfunction "1_1") (pintype "passive"))
      (node (ref "R9") (pin "1") (pinfunction "1_1") (pintype "passive"))
    )
    (net (code "72") (name "Net-(U$13-IO18)") (class "Default")
      (node (ref "R3") (pin "1") (pinfunction "1_1") (pintype "passive"))
      (node (ref "U$13") (pin "30") (pinfunction "IO18_30") (pintype "bidirectional"))
    )
    (net (code "73") (name "unconnected-(74HC595#3-Q7S-Pad9)") (class "Default")
      (node (ref "74HC595#3") (pin "9") (pinfunction "Q7S_9") (pintype "bidirectional"))
    )
    (net (code "74") (name "unconnected-(L293DD-IN3-Pad12)") (class "Default")
      (node (ref "L293DD") (pin "12") (pinfunction "IN3_12") (pintype "bidirectional"))
    )
    (net (code "75") (name "unconnected-(L293DD-OUT3-Pad13)") (class "Default")
      (node (ref "L293DD") (pin "13") (pinfunction "OUT3_13") (pintype "bidirectional"))
    )
    (net (code "76") (name "unconnected-(LTC3633-PGOOD1-Pad4)") (class "Default")
      (node (ref "LTC3633") (pin "4") (pinfunction "PGOOD1_4") (pintype "bidirectional"))
    )
    (net (code "77") (name "unconnected-(LTC3633-PGOOD2-Pad11)") (class "Default")
      (node (ref "LTC3633") (pin "11") (pinfunction "PGOOD2_11") (pintype "bidirectional"))
    )
    (net (code "78") (name "unconnected-(LTC3633-TRACKSS1-Pad2)") (class "Default")
      (node (ref "LTC3633") (pin "2") (pinfunction "TRACKSS1_2") (pintype "bidirectional"))
    )
    (net (code "79") (name "unconnected-(LTC3633-TRACKSS2-Pad13)") (class "Default")
      (node (ref "LTC3633") (pin "13") (pinfunction "TRACKSS2_13") (pintype "bidirectional"))
    )
    (net (code "80") (name "unconnected-(LTC3633-_SW1-Pad27)") (class "Default")
      (node (ref "LTC3633") (pin "27") (pinfunction "_SW1_27") (pintype "bidirectional"))
    )
    (net (code "81") (name "unconnected-(LTC3633-_SW2-Pad17)") (class "Default")
      (node (ref "LTC3633") (pin "17") (pinfunction "_SW2_17") (pintype "bidirectional"))
    )
    (net (code "82") (name "unconnected-(LTC3633-_VIN1-Pad25)") (class "Default")
      (node (ref "LTC3633") (pin "25") (pinfunction "_VIN1_25") (pintype "bidirectional"))
    )
    (net (code "83") (name "unconnected-(LTC3633-_VIN2-Pad19)") (class "Default")
      (node (ref "LTC3633") (pin "19") (pinfunction "_VIN2_19") (pintype "bidirectional"))
    )
    (net (code "84") (name "unconnected-(U$13-CLK-Pad20)") (class "Default")
      (node (ref "U$13") (pin "20") (pinfunction "CLK_20") (pintype "bidirectional"))
    )
    (net (code "85") (name "unconnected-(U$13-CMD-Pad19)") (class "Default")
      (node (ref "U$13") (pin "19") (pinfunction "CMD_19") (pintype "bidirectional"))
    )
    (net (code "86") (name "unconnected-(U$13-IO2-Pad24)") (class "Default")
      (node (ref "U$13") (pin "24") (pinfunction "IO2_24") (pintype "bidirectional"))
    )
    (net (code "87") (name "unconnected-(U$13-IO4-Pad26)") (class "Default")
      (node (ref "U$13") (pin "26") (pinfunction "IO4_26") (pintype "bidirectional"))
    )
    (net (code "88") (name "unconnected-(U$13-IO22-Pad36)") (class "Default")
      (node (ref "U$13") (pin "36") (pinfunction "IO22_36") (pintype "bidirectional"))
    )
    (net (code "89") (name "unconnected-(U$13-IO23-Pad37)") (class "Default")
      (node (ref "U$13") (pin "37") (pinfunction "IO23_37") (pintype "bidirectional"))
    )
    (net (code "90") (name "unconnected-(U$13-IO32-Pad8)") (class "Default")
      (node (ref "U$13") (pin "8") (pinfunction "IO32_8") (pintype "bidirectional"))
    )
    (net (code "91") (name "unconnected-(U$13-IO34-Pad6)") (class "Default")
      (node (ref "U$13") (pin "6") (pinfunction "IO34_6") (pintype "bidirectional"))
    )
    (net (code "92") (name "unconnected-(U$13-IO35-Pad7)") (class "Default")
      (node (ref "U$13") (pin "7") (pinfunction "IO35_7") (pintype "bidirectional"))
    )
    (net (code "93") (name "unconnected-(U$13-SD0-Pad21)") (class "Default")
      (node (ref "U$13") (pin "21") (pinfunction "SD0_21") (pintype "bidirectional"))
    )
    (net (code "94") (name "unconnected-(U$13-SD1-Pad22)") (class "Default")
      (node (ref "U$13") (pin "22") (pinfunction "SD1_22") (pintype "bidirectional"))
    )
    (net (code "95") (name "unconnected-(U$13-SD2-Pad17)") (class "Default")
      (node (ref "U$13") (pin "17") (pinfunction "SD2_17") (pintype "bidirectional"))
    )
    (net (code "96") (name "unconnected-(U$13-SD3-Pad18)") (class "Default")
      (node (ref "U$13") (pin "18") (pinfunction "SD3_18") (pintype "bidirectional"))
    )
    (net (code "97") (name "unconnected-(U$13-SVN-Pad5)") (class "Default")
      (node (ref "U$13") (pin "5") (pinfunction "SVN_5") (pintype "bidirectional"))
    )
    (net (code "98") (name "unconnected-(U$13-SVP-Pad4)") (class "Default")
      (node (ref "U$13") (pin "4") (pinfunction "SVP_4") (pintype "bidirectional"))
    )
    (net (code "99") (name "unconnected-(USB-C-PadNC{slash}3V3)") (class "Default")
      (node (ref "USB-C") (pin "NC/3V3") (pinfunction "NC/3V3_NC/3V3") (pintype "bidirectional"))
    )
    (net (code "100") (name "unconnected-(USB-C-PadNC{slash}M1)") (class "Default")
      (node (ref "USB-C") (pin "NC/M1") (pinfunction "NC/M1_NC/M1") (pintype "bidirectional"))
    )
    (net (code "101") (name "unconnected-(USB-C-PadRX0)") (class "Default")
      (node (ref "USB-C") (pin "RX0") (pinfunction "RX0_RX0") (pintype "bidirectional"))
    )
    (net (code "102") (name "unconnected-(USB-C-PadTX0)") (class "Default")
      (node (ref "USB-C") (pin "TX0") (pinfunction "TX0_TX0") (pintype "bidirectional"))
    )
  )
)
